# Potentiometer.net
KiCad netlist of a schematic drawn in Altium Designer
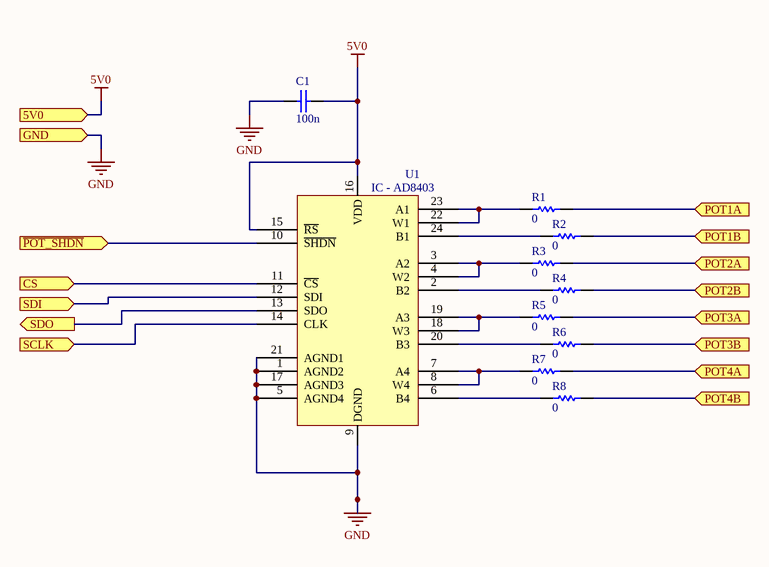
[diagram p0: Potentiometer.SchDoc]

(export (version "E")
  (design (tool "Eeschema 10.0.6"))
  (components
    (comp (ref "C1")
      (value "100n")
      (footprint "CS-0603")
      (fields
        (field (name "TOLERANCE") "10%")
        (field (name "VOLTAGE") "16V")
        (field (name "Comment") "CS - CAPACITOR")
      )
      (libsource (lib "CHINOOK_LIBRARY") (part "CS - CAPACITOR"))
    )
    (comp (ref "R1")
      (value "0")
      (footprint "RS-0402")
      (fields
        (field (name "TOLERANCE") "RES TOL")
        (field (name "POWER") "RES POWER")
        (field (name "Comment") "RS - RESISTOR")
      )
      (libsource (lib "CHINOOK_LIBRARY") (part "RS - RESISTOR"))
    )
    (comp (ref "R2")
      (value "0")
      (footprint "RS-0402")
      (fields
        (field (name "TOLERANCE") "RES TOL")
        (field (name "POWER") "RES POWER")
        (field (name "Comment") "RS - RESISTOR")
      )
      (libsource (lib "CHINOOK_LIBRARY") (part "RS - RESISTOR"))
    )
    (comp (ref "R3")
      (value "0")
      (footprint "RS-0402")
      (fields
        (field (name "TOLERANCE") "RES TOL")
        (field (name "POWER") "RES POWER")
        (field (name "Comment") "RS - RESISTOR")
      )
      (libsource (lib "CHINOOK_LIBRARY") (part "RS - RESISTOR"))
    )
    (comp (ref "R4")
      (value "0")
      (footprint "RS-0402")
      (fields
        (field (name "TOLERANCE") "RES TOL")
        (field (name "POWER") "RES POWER")
        (field (name "Comment") "RS - RESISTOR")
      )
      (libsource (lib "CHINOOK_LIBRARY") (part "RS - RESISTOR"))
    )
    (comp (ref "R5")
      (value "0")
      (footprint "RS-0402")
      (fields
        (field (name "TOLERANCE") "RES TOL")
        (field (name "POWER") "RES POWER")
        (field (name "Comment") "RS - RESISTOR")
      )
      (libsource (lib "CHINOOK_LIBRARY") (part "RS - RESISTOR"))
    )
    (comp (ref "R6")
      (value "0")
      (footprint "RS-0402")
      (fields
        (field (name "TOLERANCE") "RES TOL")
        (field (name "POWER") "RES POWER")
        (field (name "Comment") "RS - RESISTOR")
      )
      (libsource (lib "CHINOOK_LIBRARY") (part "RS - RESISTOR"))
    )
    (comp (ref "R7")
      (value "0")
      (footprint "RS-0402")
      (fields
        (field (name "TOLERANCE") "RES TOL")
        (field (name "POWER") "RES POWER")
        (field (name "Comment") "RS - RESISTOR")
      )
      (libsource (lib "CHINOOK_LIBRARY") (part "RS - RESISTOR"))
    )
    (comp (ref "R8")
      (value "0")
      (footprint "RS-0402")
      (fields
        (field (name "TOLERANCE") "RES TOL")
        (field (name "POWER") "RES POWER")
        (field (name "Comment") "RS - RESISTOR")
      )
      (libsource (lib "CHINOOK_LIBRARY") (part "RS - RESISTOR"))
    )
    (comp (ref "U1")
      (value "IC - AD8403")
      (footprint "IC-SOIC-24")
      (description "DIGITAL POTENTIOMETER")
      (libsource (lib "CHINOOK_LIBRARY") (part "IC - AD8403"))
    )
  )
  (nets
    (net (code "1") (name "/CS") (class "Default")
      (node (ref "U1") (pin "11") (pinfunction "~{CS}_11") (pintype "passive"))
    )
    (net (code "2") (name "/POT1A") (class "Default")
      (node (ref "R1") (pin "1") (pinfunction "1_1") (pintype "passive"))
    )
    (net (code "3") (name "/POT1B") (class "Default")
      (node (ref "R2") (pin "1") (pinfunction "1_1") (pintype "passive"))
    )
    (net (code "4") (name "/POT2A") (class "Default")
      (node (ref "R3") (pin "1") (pinfunction "1_1") (pintype "passive"))
    )
    (net (code "5") (name "/POT2B") (class "Default")
      (node (ref "R4") (pin "1") (pinfunction "1_1") (pintype "passive"))
    )
    (net (code "6") (name "/POT3A") (class "Default")
      (node (ref "R5") (pin "1") (pinfunction "1_1") (pintype "passive"))
    )
    (net (code "7") (name "/POT3B") (class "Default")
      (node (ref "R6") (pin "1") (pinfunction "1_1") (pintype "passive"))
    )
    (net (code "8") (name "/POT4A") (class "Default")
      (node (ref "R7") (pin "1") (pinfunction "1_1") (pintype "passive"))
    )
    (net (code "9") (name "/POT4B") (class "Default")
      (node (ref "R8") (pin "1") (pinfunction "1_1") (pintype "passive"))
    )
    (net (code "10") (name "/SCLK") (class "Default")
      (node (ref "U1") (pin "14") (pinfunction "CLK_14") (pintype "passive"))
    )
    (net (code "11") (name "/SDI") (class "Default")
      (node (ref "U1") (pin "12") (pinfunction "SDI_12") (pintype "passive"))
    )
    (net (code "12") (name "/SDO") (class "Default")
      (node (ref "U1") (pin "13") (pinfunction "SDO_13") (pintype "passive"))
    )
    (net (code "13") (name "/~{POT_SHDN}") (class "Default")
      (node (ref "U1") (pin "10") (pinfunction "~{SHDN}_10") (pintype "passive"))
    )
    (net (code "14") (name "5V0") (class "Default")
      (node (ref "C1") (pin "1") (pinfunction "1_1") (pintype "passive"))
      (node (ref "U1") (pin "15") (pinfunction "~{RS}_15") (pintype "passive"))
      (node (ref "U1") (pin "16") (pinfunction "VDD_16") (pintype "passive"))
    )
    (net (code "15") (name "GND") (class "Default")
      (node (ref "C1") (pin "2") (pinfunction "2_2") (pintype "passive"))
      (node (ref "U1") (pin "1") (pinfunction "AGND2_1") (pintype "passive"))
      (node (ref "U1") (pin "17") (pinfunction "AGND3_17") (pintype "passive"))
      (node (ref "U1") (pin "21") (pinfunction "AGND1_21") (pintype "passive"))
      (node (ref "U1") (pin "5") (pinfunction "AGND4_5") (pintype "passive"))
      (node (ref "U1") (pin "9") (pinfunction "DGND_9") (pintype "passive"))
    )
    (net (code "16") (name "Net-(U1-A1)") (class "Default")
      (node (ref "R1") (pin "2") (pinfunction "2_2") (pintype "passive"))
      (node (ref "U1") (pin "22") (pinfunction "W1_22") (pintype "passive"))
      (node (ref "U1") (pin "23") (pinfunction "A1_23") (pintype "passive"))
    )
    (net (code "17") (name "Net-(U1-A2)") (class "Default")
      (node (ref "R3") (pin "2") (pinfunction "2_2") (pintype "passive"))
      (node (ref "U1") (pin "3") (pinfunction "A2_3") (pintype "passive"))
      (node (ref "U1") (pin "4") (pinfunction "W2_4") (pintype "passive"))
    )
    (net (code "18") (name "Net-(U1-A3)") (class "Default")
      (node (ref "R5") (pin "2") (pinfunction "2_2") (pintype "passive"))
      (node (ref "U1") (pin "18") (pinfunction "W3_18") (pintype "passive"))
      (node (ref "U1") (pin "19") (pinfunction "A3_19") (pintype "passive"))
    )
    (net (code "19") (name "Net-(U1-A4)") (class "Default")
      (node (ref "R7") (pin "2") (pinfunction "2_2") (pintype "passive"))
      (node (ref "U1") (pin "7") (pinfunction "A4_7") (pintype "passive"))
      (node (ref "U1") (pin "8") (pinfunction "W4_8") (pintype "passive"))
    )
    (net (code "20") (name "Net-(U1-B1)") (class "Default")
      (node (ref "R2") (pin "2") (pinfunction "2_2") (pintype "passive"))
      (node (ref "U1") (pin "24") (pinfunction "B1_24") (pintype "passive"))
    )
    (net (code "21") (name "Net-(U1-B2)") (class "Default")
      (node (ref "R4") (pin "2") (pinfunction "2_2") (pintype "passive"))
      (node (ref "U1") (pin "2") (pinfunction "B2_2") (pintype "passive"))
    )
    (net (code "22") (name "Net-(U1-B3)") (class "Default")
      (node (ref "R6") (pin "2") (pinfunction "2_2") (pintype "passive"))
      (node (ref "U1") (pin "20") (pinfunction "B3_20") (pintype "passive"))
    )
    (net (code "23") (name "Net-(U1-B4)") (class "Default")
      (node (ref "R8") (pin "2") (pinfunction "2_2") (pintype "passive"))
      (node (ref "U1") (pin "6") (pinfunction "B4_6") (pintype "passive"))
    )
  )
)
